# ESP32__2023-03-20.net
KiCad netlist of a schematic drawn in Altium Designer
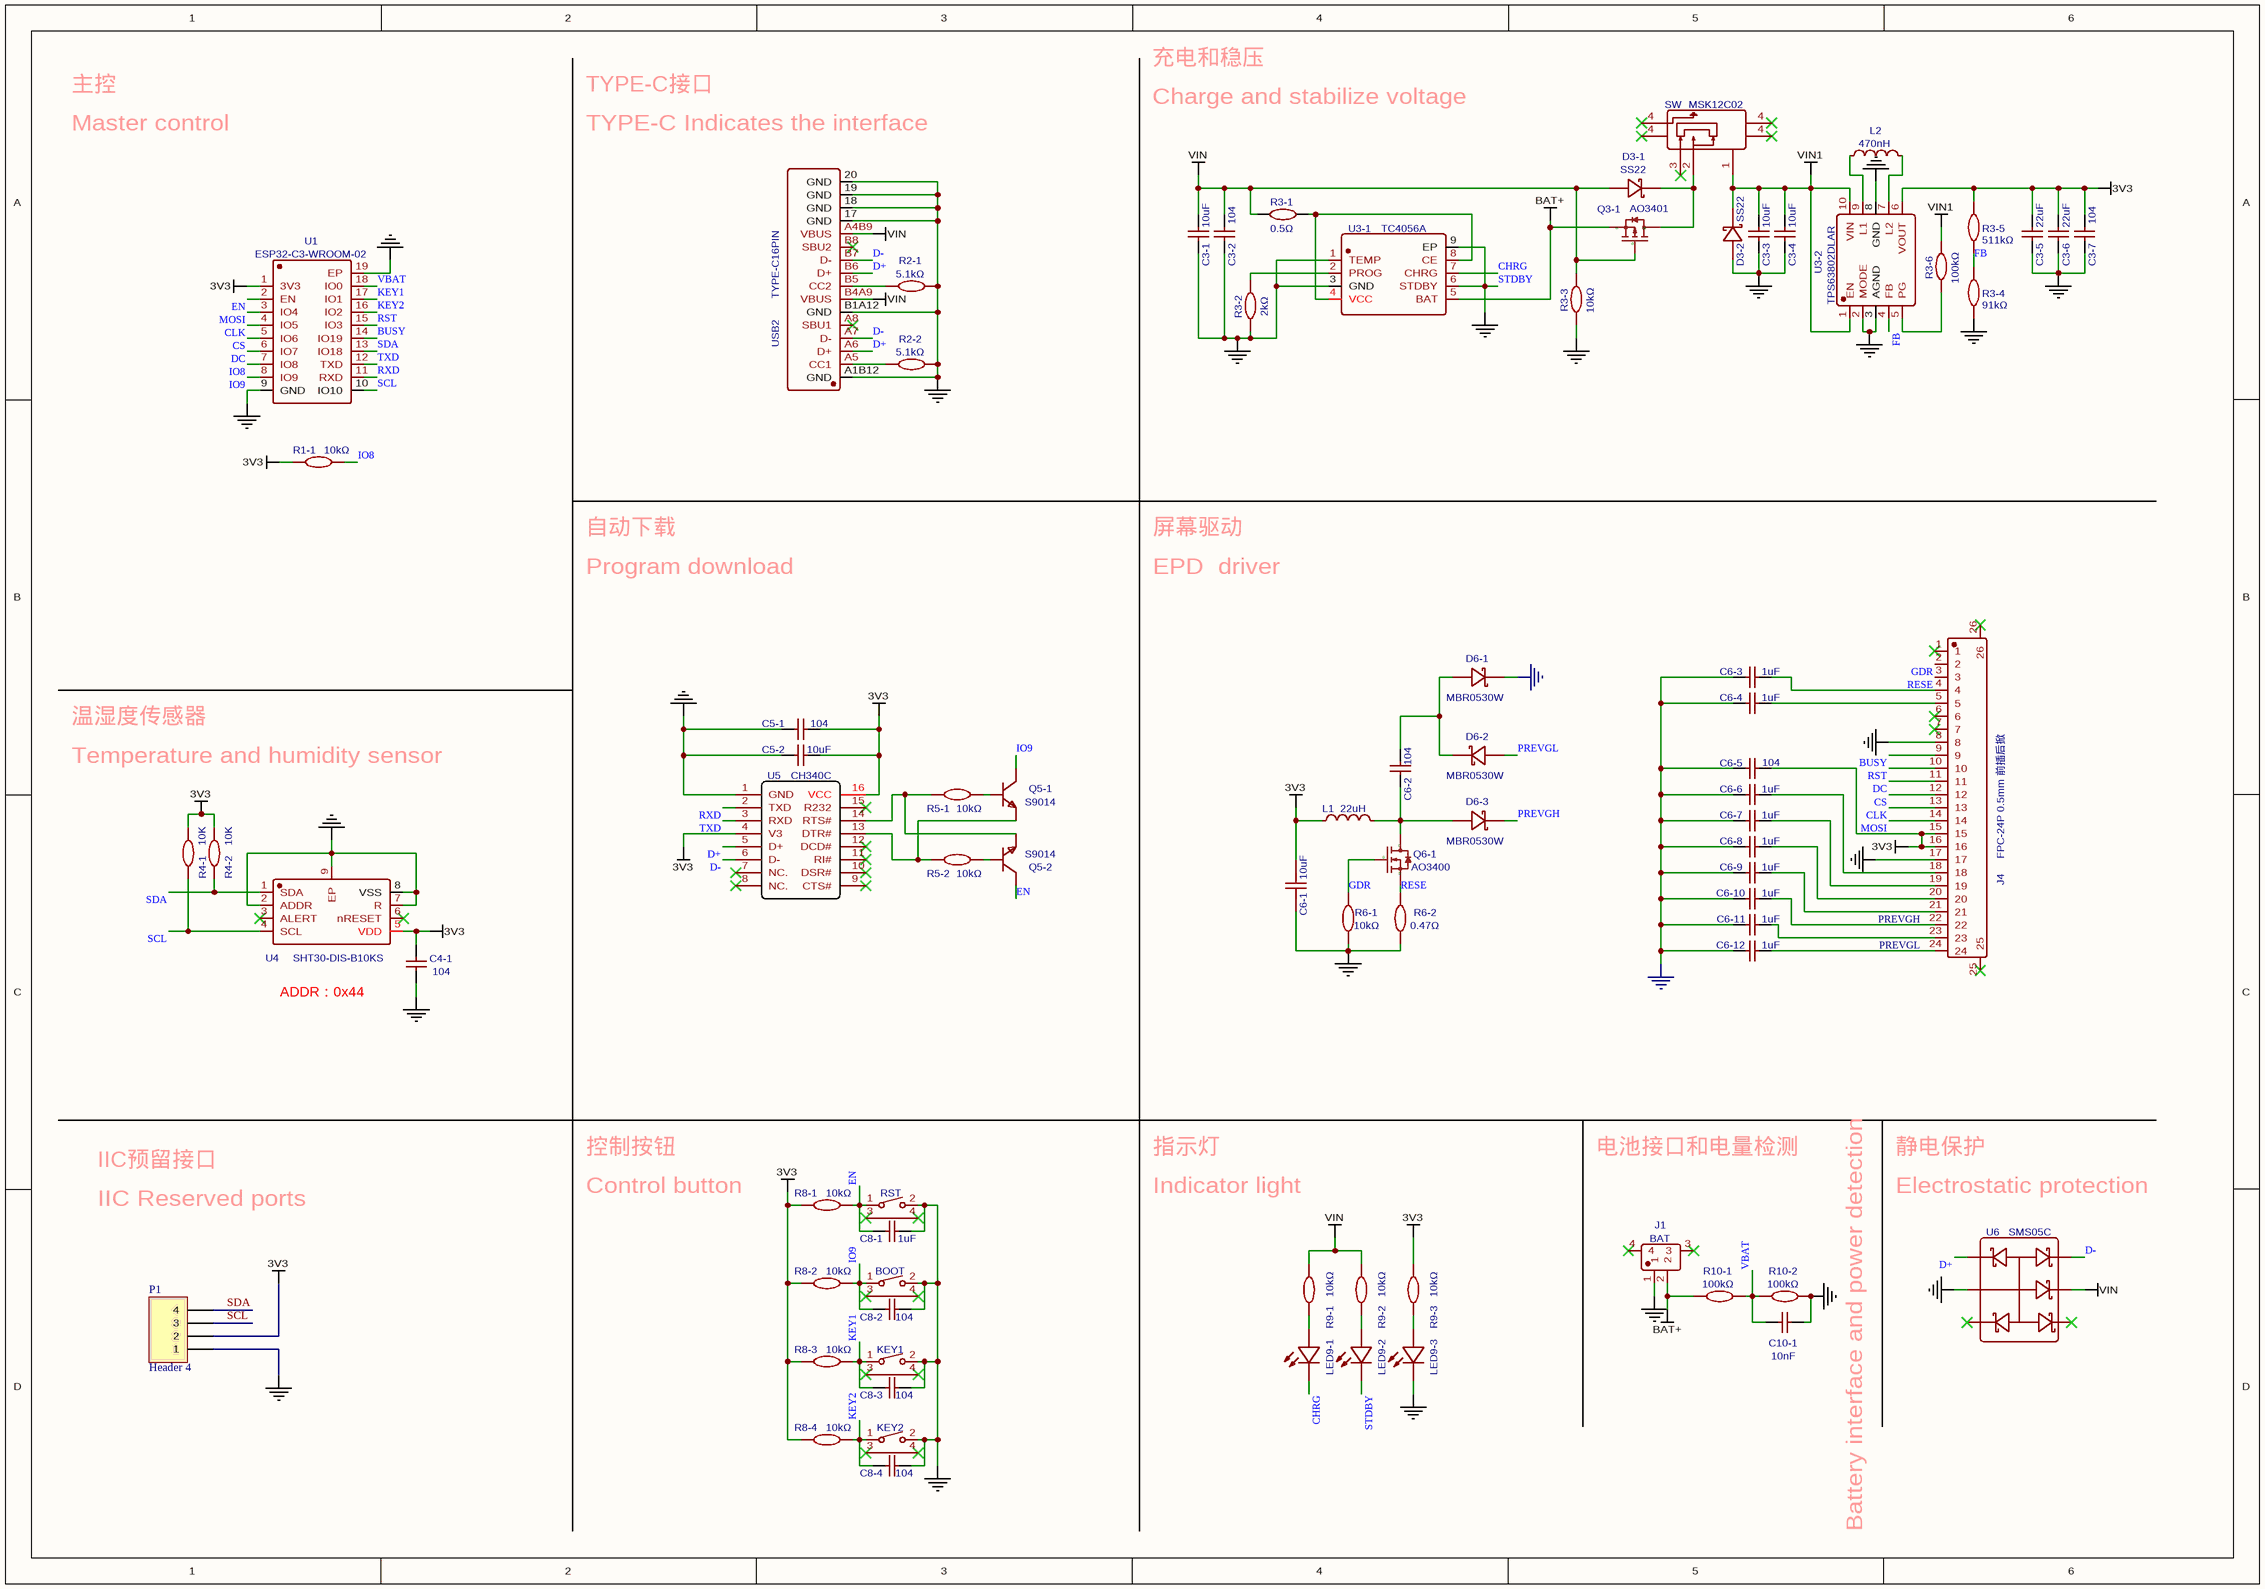
[diagram p0: ESP32墨水屏开发板_2023-03-20.schdoc]

(export (version "E")
  (design (tool "Eeschema 10.0.6"))
  (components
    (comp (ref "BOOT")
      (value "UK-B0246-SP25Y")
      (footprint "SW-SMD_UK-B0246-SP25Y")
      (fields (field (name "BOM_SUPPLIER PART") "C493279") (field (name "CONTRIBUTOR") "LCSC"))
      (libsource (lib "altium-import") (part "root_0_UK-B0246-SP25Y_"))
    )
    (comp (ref "C3-1")
      (value "10uF")
      (footprint "C0603")
      (fields
        (field (name "BOM_MANUFACTURER PART") "CC0603MRX5R5BB106")
        (field (name "BOM_SUPPLIER PART") "C109454")
      )
      (libsource (lib "altium-import") (part "root_1_10uF_"))
    )
    (comp (ref "C3-2")
      (value "104")
      (footprint "C0603")
      (fields
        (field (name "BOM_MANUFACTURER PART") "C0603C104K5RACTU")
        (field (name "BOM_SUPPLIER PART") "C127833")
        (field (name "CONTRIBUTOR") "LCSC")
      )
      (libsource (lib "altium-import") (part "root_1_104_"))
    )
    (comp (ref "C3-3")
      (value "10uF")
      (footprint "C0603")
      (fields
        (field (name "BOM_MANUFACTURER PART") "CC0603MRX5R5BB106")
        (field (name "BOM_SUPPLIER PART") "C109454")
      )
      (libsource (lib "altium-import") (part "root_1_10uF_"))
    )
    (comp (ref "C3-4")
      (value "10uF")
      (footprint "C0603")
      (fields
        (field (name "BOM_MANUFACTURER PART") "CC0603MRX5R5BB106")
        (field (name "BOM_SUPPLIER PART") "C109454")
      )
      (libsource (lib "altium-import") (part "root_1_10uF_"))
    )
    (comp (ref "C3-5")
      (value "22uF")
      (footprint "C0603")
      (fields
        (field (name "BOM_MANUFACTURER PART") "CC0603MRX5R5BB106")
        (field (name "BOM_SUPPLIER PART") "C109454")
      )
      (libsource (lib "altium-import") (part "root_1_22uF_"))
    )
    (comp (ref "C3-6")
      (value "22uF")
      (footprint "C0603")
      (fields
        (field (name "BOM_MANUFACTURER PART") "CC0603MRX5R5BB106")
        (field (name "BOM_SUPPLIER PART") "C109454")
      )
      (libsource (lib "altium-import") (part "root_1_22uF_"))
    )
    (comp (ref "C3-7")
      (value "104")
      (footprint "C0603")
      (fields
        (field (name "BOM_MANUFACTURER PART") "C0603C104K5RACTU")
        (field (name "BOM_SUPPLIER PART") "C127833")
        (field (name "CONTRIBUTOR") "LCSC")
      )
      (libsource (lib "altium-import") (part "root_1_104_"))
    )
    (comp (ref "C4-1")
      (value "104")
      (footprint "C0603")
      (fields
        (field (name "BOM_MANUFACTURER PART") "C0603C104K5RACTU")
        (field (name "BOM_SUPPLIER PART") "C127833")
        (field (name "CONTRIBUTOR") "LCSC")
      )
      (libsource (lib "altium-import") (part "root_1_104_"))
    )
    (comp (ref "C5-1")
      (value "104")
      (footprint "C0603")
      (fields
        (field (name "BOM_MANUFACTURER PART") "C0603C104K5RACTU")
        (field (name "BOM_SUPPLIER PART") "C127833")
        (field (name "CONTRIBUTOR") "LCSC")
      )
      (libsource (lib "altium-import") (part "root_2_104_"))
    )
    (comp (ref "C5-2")
      (value "10uF")
      (footprint "C0603")
      (fields
        (field (name "BOM_MANUFACTURER PART") "CC0603MRX5R5BB106")
        (field (name "BOM_SUPPLIER PART") "C109454")
      )
      (libsource (lib "altium-import") (part "root_2_10uF_"))
    )
    (comp (ref "C6-1")
      (value "10uF")
      (footprint "C0805")
      (fields
        (field (name "BOM_SUPPLIER PART") "C2844304")
        (field (name "BOM_MANUFACTURER PART") "C0805X6S106K350NT")
        (field (name "CONTRIBUTOR") "lcsc")
      )
      (libsource (lib "") (part "root_1_10uF__1"))
    )
    (comp (ref "C6-2")
      (value "104")
      (footprint "C0603")
      (fields
        (field (name "BOM_MANUFACTURER PART") "C0603C104K5RACTU")
        (field (name "BOM_SUPPLIER PART") "C127833")
        (field (name "CONTRIBUTOR") "LCSC")
      )
      (libsource (lib "altium-import") (part "root_1_104_"))
    )
    (comp (ref "C6-3")
      (value "1uF")
      (footprint "C0603")
      (fields
        (field (name "BOM_MANUFACTURER PART") "CC0603KRX5R7BB105")
        (field (name "BOM_SUPPLIER PART") "C106215")
        (field (name "CONTRIBUTOR") "LCSC")
      )
      (libsource (lib "altium-import") (part "root_0_1uF_"))
    )
    (comp (ref "C6-4")
      (value "1uF")
      (footprint "C0603")
      (fields
        (field (name "BOM_MANUFACTURER PART") "CC0603KRX5R7BB105")
        (field (name "BOM_SUPPLIER PART") "C106215")
        (field (name "CONTRIBUTOR") "LCSC")
      )
      (libsource (lib "altium-import") (part "root_0_1uF_"))
    )
    (comp (ref "C6-5")
      (value "104")
      (footprint "C0603")
      (fields
        (field (name "BOM_MANUFACTURER PART") "C0603C104K5RACTU")
        (field (name "BOM_SUPPLIER PART") "C127833")
        (field (name "CONTRIBUTOR") "LCSC")
      )
      (libsource (lib "altium-import") (part "root_2_104_"))
    )
    (comp (ref "C6-6")
      (value "1uF")
      (footprint "C0603")
      (fields
        (field (name "BOM_MANUFACTURER PART") "CC0603KRX5R7BB105")
        (field (name "BOM_SUPPLIER PART") "C106215")
        (field (name "CONTRIBUTOR") "LCSC")
      )
      (libsource (lib "altium-import") (part "root_0_1uF_"))
    )
    (comp (ref "C6-7")
      (value "1uF")
      (footprint "C0603")
      (fields
        (field (name "BOM_MANUFACTURER PART") "CC0603KRX5R7BB105")
        (field (name "BOM_SUPPLIER PART") "C106215")
        (field (name "CONTRIBUTOR") "LCSC")
      )
      (libsource (lib "altium-import") (part "root_0_1uF_"))
    )
    (comp (ref "C6-8")
      (value "1uF")
      (footprint "C0603")
      (fields
        (field (name "BOM_MANUFACTURER PART") "CC0603KRX5R7BB105")
        (field (name "BOM_SUPPLIER PART") "C106215")
        (field (name "CONTRIBUTOR") "LCSC")
      )
      (libsource (lib "altium-import") (part "root_0_1uF_"))
    )
    (comp (ref "C6-9")
      (value "1uF")
      (footprint "C0603")
      (fields
        (field (name "BOM_MANUFACTURER PART") "CC0603KRX5R7BB105")
        (field (name "BOM_SUPPLIER PART") "C106215")
        (field (name "CONTRIBUTOR") "LCSC")
      )
      (libsource (lib "altium-import") (part "root_0_1uF_"))
    )
    (comp (ref "C6-10")
      (value "1uF")
      (footprint "C0603")
      (fields
        (field (name "BOM_MANUFACTURER PART") "CC0603KRX5R7BB105")
        (field (name "BOM_SUPPLIER PART") "C106215")
        (field (name "CONTRIBUTOR") "LCSC")
      )
      (libsource (lib "altium-import") (part "root_0_1uF_"))
    )
    (comp (ref "C6-11")
      (value "1uF")
      (footprint "C0603")
      (fields
        (field (name "BOM_MANUFACTURER PART") "CC0603KRX5R7BB105")
        (field (name "BOM_SUPPLIER PART") "C106215")
        (field (name "CONTRIBUTOR") "LCSC")
      )
      (libsource (lib "altium-import") (part "root_0_1uF_"))
    )
    (comp (ref "C6-12")
      (value "1uF")
      (footprint "C0603")
      (fields
        (field (name "BOM_MANUFACTURER PART") "CC0603KRX5R7BB105")
        (field (name "BOM_SUPPLIER PART") "C106215")
        (field (name "CONTRIBUTOR") "LCSC")
      )
      (libsource (lib "altium-import") (part "root_0_1uF_"))
    )
    (comp (ref "C8-1")
      (value "1uF")
      (footprint "C0603")
      (fields
        (field (name "BOM_MANUFACTURER PART") "CC0603MRX5R5BB106")
        (field (name "BOM_SUPPLIER PART") "C109454")
      )
      (libsource (lib "altium-import") (part "root_2_1uF_"))
    )
    (comp (ref "C8-2")
      (value "104")
      (footprint "C0603")
      (fields
        (field (name "BOM_MANUFACTURER PART") "C0603C104K5RACTU")
        (field (name "BOM_SUPPLIER PART") "C127833")
        (field (name "CONTRIBUTOR") "LCSC")
      )
      (libsource (lib "altium-import") (part "root_0_104_"))
    )
    (comp (ref "C8-3")
      (value "104")
      (footprint "C0603")
      (fields
        (field (name "BOM_MANUFACTURER PART") "C0603C104K5RACTU")
        (field (name "BOM_SUPPLIER PART") "C127833")
        (field (name "CONTRIBUTOR") "LCSC")
      )
      (libsource (lib "altium-import") (part "root_0_104_"))
    )
    (comp (ref "C8-4")
      (value "104")
      (footprint "C0603")
      (fields
        (field (name "BOM_MANUFACTURER PART") "C0603C104K5RACTU")
        (field (name "BOM_SUPPLIER PART") "C127833")
        (field (name "CONTRIBUTOR") "LCSC")
      )
      (libsource (lib "altium-import") (part "root_0_104_"))
    )
    (comp (ref "C10-1")
      (value "10nF")
      (footprint "C0603")
      (fields
        (field (name "BOM_MANUFACTURER PART") "C0603C104K5RACTU")
        (field (name "BOM_SUPPLIER PART") "C127833")
        (field (name "CONTRIBUTOR") "LCSC")
      )
      (libsource (lib "altium-import") (part "root_2_10nF_"))
    )
    (comp (ref "D3-1")
      (value "SS22")
      (footprint "SMA_L4.3-W2.5-LS5.0-R-RD")
      (fields (field (name "BOM_SUPPLIER PART") "C727054") (field (name "CONTRIBUTOR") "LCSC"))
      (libsource (lib "altium-import") (part "root_2_SS22_"))
    )
    (comp (ref "D3-2")
      (value "SS22")
      (footprint "SMA_L4.3-W2.5-LS5.0-R-RD")
      (fields (field (name "BOM_SUPPLIER PART") "C727054") (field (name "CONTRIBUTOR") "LCSC"))
      (libsource (lib "altium-import") (part "root_3_SS22_"))
    )
    (comp (ref "D6-1")
      (value "MBR0530W")
      (footprint "SOD-123_L2.7-W1.7-LS3.8-RD")
      (fields
        (field (name "BOM_SUPPLIER PART") "C2965565")
        (field (name "BOM_MANUFACTURER PART") "MBR0530W B3")
        (field (name "CONTRIBUTOR") "lcsc")
      )
      (libsource (lib "altium-import") (part "root_2_MBR0530W_"))
    )
    (comp (ref "D6-2")
      (value "MBR0530W")
      (footprint "SOD-123_L2.7-W1.7-LS3.8-RD")
      (fields
        (field (name "BOM_SUPPLIER PART") "C2965565")
        (field (name "BOM_MANUFACTURER PART") "MBR0530W B3")
        (field (name "CONTRIBUTOR") "lcsc")
      )
      (libsource (lib "altium-import") (part "root_0_MBR0530W_"))
    )
    (comp (ref "D6-3")
      (value "MBR0530W")
      (footprint "SOD-123_L2.7-W1.7-LS3.8-RD")
      (fields
        (field (name "BOM_SUPPLIER PART") "C2965565")
        (field (name "BOM_MANUFACTURER PART") "MBR0530W B3")
        (field (name "CONTRIBUTOR") "lcsc")
      )
      (libsource (lib "altium-import") (part "root_2_MBR0530W_"))
    )
    (comp (ref "J1")
      (value "BAT")
      (footprint "CONN-SMD_XH2.54-2PSMD")
      (fields
        (field (name "BOM_SUPPLIER PART") "C9900001015")
        (field (name "BOM_MANUFACTURER PART") "XH2.54-2PSMD")
        (field (name "CONTRIBUTOR") "LCSC")
      )
      (libsource (lib "altium-import") (part "root_1_BAT_"))
    )
    (comp (ref "J4")
      (value "FPC-24P 0.5mm 前插后掀")
      (footprint "FPC-SMD_X05A26H24G")
      (fields
        (field (name "BOM_SUPPLIER PART") "C519265")
        (field (name "BOM_MANUFACTURER PART") "X05A26H24G")
        (field (name "CONTRIBUTOR") "LCSC")
      )
      (libsource (lib "altium-import") (part "root_0_FPC-24P 0.5mm 前插后掀_"))
    )
    (comp (ref "KEY1")
      (value "UK-B0246-SP25Y")
      (footprint "SW-SMD_UK-B0246-SP25Y")
      (fields (field (name "BOM_SUPPLIER PART") "C493279") (field (name "CONTRIBUTOR") "LCSC"))
      (libsource (lib "altium-import") (part "root_0_UK-B0246-SP25Y_"))
    )
    (comp (ref "KEY2")
      (value "UK-B0246-SP25Y")
      (footprint "SW-SMD_UK-B0246-SP25Y")
      (fields (field (name "BOM_SUPPLIER PART") "C493279") (field (name "CONTRIBUTOR") "LCSC"))
      (libsource (lib "altium-import") (part "root_0_UK-B0246-SP25Y_"))
    )
    (comp (ref "L1")
      (value "22uH")
      (footprint "IND-SMD_L2.5-W2.0_SWPA252012S")
      (fields
        (field (name "BOM_SUPPLIER PART") "C363229")
        (field (name "BOM_MANUFACTURER PART") "SMNR252012-220MT")
        (field (name "CONTRIBUTOR") "LCSC")
      )
      (libsource (lib "altium-import") (part "root_0_22uH_"))
    )
    (comp (ref "L2")
      (value "470nH")
      (footprint "L0805")
      (fields
        (field (name "BOM_MANUFACTURER PART") "SDFL2012LR47KTF")
        (field (name "BOM_SUPPLIER PART") "C48556")
      )
      (libsource (lib "altium-import") (part "root_0_470nH_"))
    )
    (comp (ref "LED9-1")
      (value "RED")
      (footprint "LED0603-RD")
      (fields
        (field (name "BOM_SUPPLIER PART") "C401120")
        (field (name "BOM_MANUFACTURER PART") "MHT192JRCT")
        (field (name "CONTRIBUTOR") "LCSC")
      )
      (libsource (lib "altium-import") (part "root_1_RED_"))
    )
    (comp (ref "LED9-2")
      (value "RED")
      (footprint "LED0603-RD")
      (fields
        (field (name "BOM_SUPPLIER PART") "C401120")
        (field (name "BOM_MANUFACTURER PART") "MHT192JRCT")
        (field (name "CONTRIBUTOR") "LCSC")
      )
      (libsource (lib "altium-import") (part "root_1_RED_"))
    )
    (comp (ref "LED9-3")
      (value "RED")
      (footprint "LED0603-RD")
      (fields
        (field (name "BOM_SUPPLIER PART") "C401120")
        (field (name "BOM_MANUFACTURER PART") "MHT192JRCT")
        (field (name "CONTRIBUTOR") "LCSC")
      )
      (libsource (lib "altium-import") (part "root_1_RED_"))
    )
    (comp (ref "P1")
      (value "Header 4")
      (footprint "HDR1X4")
      (description "Header, 4-Pin")
      (fields (field (name "PUBLISHER") "Altium Limited"))
      (libsource (lib "Miscellaneous Connectors") (part "Header 4"))
    )
    (comp (ref "Q3-1")
      (value "AO3401")
      (footprint "SOT-23-3_L2.9-W1.3-P1.90-LS2.4-BR")
      (fields (field (name "BOM_SUPPLIER PART") "C181091") (field (name "CONTRIBUTOR") "LCSC"))
      (libsource (lib "altium-import") (part "root_1_AO3401_"))
    )
    (comp (ref "Q5-1")
      (value "S9014")
      (footprint "SOT-23-3_L2.9-W1.3-P1.90-LS2.4-BR")
      (fields (field (name "BOM_SUPPLIER PART") "C2926162") (field (name "CONTRIBUTOR") "LCSC"))
      (libsource (lib "altium-import") (part "root_0_S9014_"))
    )
    (comp (ref "Q5-2")
      (value "S9014")
      (footprint "SOT-23-3_L2.9-W1.3-P1.90-LS2.4-BR")
      (fields (field (name "BOM_SUPPLIER PART") "C2926162") (field (name "CONTRIBUTOR") "LCSC"))
      (libsource (lib "") (part "root_0_S9014__1"))
    )
    (comp (ref "Q6-1")
      (value "AO3400")
      (footprint "SC-59-3_L2.9-W1.5-P0.95-LS2.5-BR")
      (fields (field (name "BOM_SUPPLIER PART") "C122850") (field (name "CONTRIBUTOR") "立创EDA官方封装库"))
      (libsource (lib "altium-import") (part "root_0_AO3400_"))
    )
    (comp (ref "R1-1")
      (value "10kΩ")
      (footprint "R0603")
      (fields
        (field (name "BOM_SUPPLIER PART") "C380762")
        (field (name "BOM_MANUFACTURER PART") "SY0603JN10KP")
        (field (name "CONTRIBUTOR") "LCSC")
      )
      (libsource (lib "altium-import") (part "root_2_10kΩ_"))
    )
    (comp (ref "R2-1")
      (value "5.1kΩ")
      (footprint "R0603")
      (fields
        (field (name "BOM_SUPPLIER PART") "C369945")
        (field (name "BOM_MANUFACTURER PART") "PTFR0603D5K10P9")
        (field (name "CONTRIBUTOR") "LCSC")
      )
      (libsource (lib "altium-import") (part "root_0_5.1kΩ_"))
    )
    (comp (ref "R2-2")
      (value "5.1kΩ")
      (footprint "R0603")
      (fields
        (field (name "BOM_SUPPLIER PART") "C369945")
        (field (name "BOM_MANUFACTURER PART") "PTFR0603D5K10P9")
        (field (name "CONTRIBUTOR") "LCSC")
      )
      (libsource (lib "altium-import") (part "root_0_5.1kΩ_"))
    )
    (comp (ref "R3-1")
      (value "0.5Ω")
      (footprint "R1206")
      (fields
        (field (name "BOM_MANUFACTURER PART") "RTT06R500FTP")
        (field (name "BOM_SUPPLIER PART") "C104947")
      )
      (libsource (lib "altium-import") (part "root_2_0.5Ω_"))
    )
    (comp (ref "R3-2")
      (value "2kΩ")
      (footprint "R0603")
      (fields
        (field (name "BOM_SUPPLIER PART") "C380762")
        (field (name "BOM_MANUFACTURER PART") "SY0603JN10KP")
        (field (name "CONTRIBUTOR") "LCSC")
      )
      (libsource (lib "altium-import") (part "root_1_2kΩ_"))
    )
    (comp (ref "R3-3")
      (value "10kΩ")
      (footprint "R0603")
      (fields
        (field (name "BOM_SUPPLIER PART") "C380762")
        (field (name "BOM_MANUFACTURER PART") "SY0603JN10KP")
        (field (name "CONTRIBUTOR") "LCSC")
      )
      (libsource (lib "altium-import") (part "root_1_10kΩ_"))
    )
    (comp (ref "R3-4")
      (value "91kΩ")
      (footprint "R0603")
      (fields
        (field (name "BOM_SUPPLIER PART") "C369945")
        (field (name "BOM_MANUFACTURER PART") "PTFR0603D5K10P9")
        (field (name "CONTRIBUTOR") "LCSC")
      )
      (libsource (lib "altium-import") (part "root_3_91kΩ_"))
    )
    (comp (ref "R3-5")
      (value "511kΩ")
      (footprint "R0603")
      (fields
        (field (name "BOM_SUPPLIER PART") "C369945")
        (field (name "BOM_MANUFACTURER PART") "PTFR0603D5K10P9")
        (field (name "CONTRIBUTOR") "LCSC")
      )
      (libsource (lib "altium-import") (part "root_3_511kΩ_"))
    )
    (comp (ref "R3-6")
      (value "100kΩ")
      (footprint "R0603")
      (fields
        (field (name "BOM_SUPPLIER PART") "C380762")
        (field (name "BOM_MANUFACTURER PART") "SY0603JN10KP")
        (field (name "CONTRIBUTOR") "LCSC")
      )
      (libsource (lib "altium-import") (part "root_1_100kΩ_"))
    )
    (comp (ref "R4-1")
      (value "10K")
      (footprint "R0603")
      (fields
        (field (name "BOM_SUPPLIER PART") "C380762")
        (field (name "BOM_MANUFACTURER PART") "SY0603JN10KP")
        (field (name "CONTRIBUTOR") "LCSC")
      )
      (libsource (lib "altium-import") (part "root_1_10K_"))
    )
    (comp (ref "R4-2")
      (value "10K")
      (footprint "R0603")
      (fields
        (field (name "BOM_SUPPLIER PART") "C380762")
        (field (name "BOM_MANUFACTURER PART") "SY0603JN10KP")
        (field (name "CONTRIBUTOR") "LCSC")
      )
      (libsource (lib "altium-import") (part "root_1_10K_"))
    )
    (comp (ref "R5-1")
      (value "10kΩ")
      (footprint "R0603")
      (fields
        (field (name "BOM_SUPPLIER PART") "C380762")
        (field (name "BOM_MANUFACTURER PART") "SY0603JN10KP")
        (field (name "CONTRIBUTOR") "LCSC")
      )
      (libsource (lib "altium-import") (part "root_0_10kΩ_"))
    )
    (comp (ref "R5-2")
      (value "10kΩ")
      (footprint "R0603")
      (fields
        (field (name "BOM_SUPPLIER PART") "C380762")
        (field (name "BOM_MANUFACTURER PART") "SY0603JN10KP")
        (field (name "CONTRIBUTOR") "LCSC")
      )
      (libsource (lib "altium-import") (part "root_0_10kΩ_"))
    )
    (comp (ref "R6-1")
      (value "10kΩ")
      (footprint "R0603")
      (fields
        (field (name "BOM_SUPPLIER PART") "C380762")
        (field (name "BOM_MANUFACTURER PART") "SY0603JN10KP")
        (field (name "CONTRIBUTOR") "LCSC")
      )
      (libsource (lib "altium-import") (part "root_1_10kΩ_"))
    )
    (comp (ref "R6-2")
      (value "0.47Ω")
      (footprint "R0603")
      (fields
        (field (name "BOM_SUPPLIER PART") "C175657")
        (field (name "BOM_MANUFACTURER PART") "CR0603F0R47P05")
        (field (name "CONTRIBUTOR") "LCSC")
      )
      (libsource (lib "altium-import") (part "root_1_0.47Ω_"))
    )
    (comp (ref "R8-1")
      (value "10kΩ")
      (footprint "R0603")
      (fields
        (field (name "BOM_SUPPLIER PART") "C380762")
        (field (name "BOM_MANUFACTURER PART") "SY0603JN10KP")
        (field (name "CONTRIBUTOR") "LCSC")
      )
      (libsource (lib "altium-import") (part "root_0_10kΩ_"))
    )
    (comp (ref "R8-2")
      (value "10kΩ")
      (footprint "R0603")
      (fields
        (field (name "BOM_SUPPLIER PART") "C380762")
        (field (name "BOM_MANUFACTURER PART") "SY0603JN10KP")
        (field (name "CONTRIBUTOR") "LCSC")
      )
      (libsource (lib "altium-import") (part "root_0_10kΩ_"))
    )
    (comp (ref "R8-3")
      (value "10kΩ")
      (footprint "R0603")
      (fields
        (field (name "BOM_SUPPLIER PART") "C380762")
        (field (name "BOM_MANUFACTURER PART") "SY0603JN10KP")
        (field (name "CONTRIBUTOR") "LCSC")
      )
      (libsource (lib "altium-import") (part "root_0_10kΩ_"))
    )
    (comp (ref "R8-4")
      (value "10kΩ")
      (footprint "R0603")
      (fields
        (field (name "BOM_SUPPLIER PART") "C380762")
        (field (name "BOM_MANUFACTURER PART") "SY0603JN10KP")
        (field (name "CONTRIBUTOR") "LCSC")
      )
      (libsource (lib "altium-import") (part "root_0_10kΩ_"))
    )
    (comp (ref "R9-1")
      (value "10kΩ")
      (footprint "R0603")
      (fields
        (field (name "BOM_SUPPLIER PART") "C380762")
        (field (name "BOM_MANUFACTURER PART") "SY0603JN10KP")
        (field (name "CONTRIBUTOR") "LCSC")
      )
      (libsource (lib "altium-import") (part "root_1_10kΩ_"))
    )
    (comp (ref "R9-2")
      (value "10kΩ")
      (footprint "R0603")
      (fields
        (field (name "BOM_SUPPLIER PART") "C380762")
        (field (name "BOM_MANUFACTURER PART") "SY0603JN10KP")
        (field (name "CONTRIBUTOR") "LCSC")
      )
      (libsource (lib "altium-import") (part "root_1_10kΩ_"))
    )
    (comp (ref "R9-3")
      (value "10kΩ")
      (footprint "R0603")
      (fields
        (field (name "BOM_SUPPLIER PART") "C380762")
        (field (name "BOM_MANUFACTURER PART") "SY0603JN10KP")
        (field (name "CONTRIBUTOR") "LCSC")
      )
      (libsource (lib "altium-import") (part "root_1_10kΩ_"))
    )
    (comp (ref "R10-1")
      (value "100kΩ")
      (footprint "R0603")
      (fields
        (field (name "BOM_SUPPLIER PART") "C269694")
        (field (name "BOM_MANUFACTURER PART") "RMC06034.7k5%N")
        (field (name "CONTRIBUTOR") "LCSC")
      )
      (libsource (lib "altium-import") (part "root_2_100kΩ_"))
    )
    (comp (ref "R10-2")
      (value "100kΩ")
      (footprint "R0603")
      (fields
        (field (name "BOM_SUPPLIER PART") "C328340")
        (field (name "BOM_MANUFACTURER PART") "AECR0603F1K00K9")
        (field (name "CONTRIBUTOR") "LCSC")
      )
      (libsource (lib "altium-import") (part "root_2_100kΩ_"))
    )
    (comp (ref "RST")
      (value "UK-B0246-SP25Y")
      (footprint "SW-SMD_UK-B0246-SP25Y")
      (fields (field (name "BOM_SUPPLIER PART") "C493279") (field (name "CONTRIBUTOR") "LCSC"))
      (libsource (lib "altium-import") (part "root_0_UK-B0246-SP25Y_"))
    )
    (comp (ref "SW")
      (value "MSK12C02")
      (footprint "SW-TH_MSK12C02")
      (fields (field (name "BOM_SUPPLIER PART") "C431540") (field (name "CONTRIBUTOR") "LCSC"))
      (libsource (lib "altium-import") (part "root_2_MSK12C02_"))
    )
    (comp (ref "U1")
      (value "ESP32-C3-WROOM-02")
      (footprint "BULETM-SMD_ESPRESSIF_ESP32-C3-WROOM-02-N4-4MB")
      (fields
        (field (name "BOM_SUPPLIER PART") "C2934560")
        (field (name "BOM_MANUFACTURER PART") "ESP32-C3-WROOM-02-N4")
        (field (name "CONTRIBUTOR") "LCSC")
      )
      (libsource (lib "altium-import") (part "root_0_ESP32-C3-WROOM-02_"))
    )
    (comp (ref "U3-1")
      (value "TC4056A")
      (footprint "SOP-8_L4.9-W3.9-P1.27-LS6.0-BL-EP")
      (fields (field (name "BOM_SUPPLIER PART") "C84051"))
      (libsource (lib "altium-import") (part "root_0_TC4056A_"))
    )
    (comp (ref "U3-2")
      (value "TPS63802DLAR")
      (footprint "VSON-10_L3.0-W2.0-P0.50-BL_TI_DLA0010A")
      (fields (field (name "BOM_SUPPLIER PART") "C2845237") (field (name "CONTRIBUTOR") "LCSC"))
      (libsource (lib "altium-import") (part "root_1_TPS63802DLAR_"))
    )
    (comp (ref "U4")
      (value "SHT30-DIS-B10KS")
      (footprint "DFN-8_L2.5-W2.5-P0.50-BL-EP")
      (fields (field (name "BOM_SUPPLIER PART") "C2687423") (field (name "CONTRIBUTOR") "LCSC"))
      (libsource (lib "altium-import") (part "root_0_SHT30-DIS-B10KS_"))
    )
    (comp (ref "U5")
      (value "CH340C")
      (footprint "SOP-16_L10.0-W3.9-P1.27-LS6.0-BL")
      (fields (field (name "BOM_SUPPLIER PART") "C84681"))
      (libsource (lib "altium-import") (part "root_0_CH340C_"))
    )
    (comp (ref "U6")
      (value "SMS05C")
      (footprint "SOT-23-6_L2.9-W1.6-P0.95-LS2.8-BL")
      (fields (field (name "BOM_SUPPLIER PART") "C2827671") (field (name "CONTRIBUTOR") "lcsc"))
      (libsource (lib "altium-import") (part "root_0_SMS05C_"))
    )
    (comp (ref "USB2")
      (value "TYPE-C16PIN")
      (footprint "USB-SMD_TYPE-C16PIN-1")
      (fields
        (field (name "BOM_SUPPLIER PART") "C2894751")
        (field (name "BOM_MANUFACTURER PART") "TYPE-C16PIN四脚插板母座5A大电流")
        (field (name "CONTRIBUTOR") "LCSC")
      )
      (libsource (lib "altium-import") (part "root_2_TYPE-C16PIN_"))
    )
  )
  (nets
    (net (code "1") (name "/BUSY") (class "Default")
      (node (ref "J4") (pin "9") (pinfunction "9_9") (pintype "passive"))
      (node (ref "U1") (pin "14") (pinfunction "IO19_14") (pintype "passive"))
    )
    (net (code "2") (name "/CHRG") (class "Default")
      (node (ref "LED9-1") (pin "1") (pinfunction "K_1") (pintype "passive"))
      (node (ref "U3-1") (pin "7") (pinfunction "CHRG_7") (pintype "passive"))
    )
    (net (code "3") (name "/CLK") (class "Default")
      (node (ref "J4") (pin "13") (pinfunction "13_13") (pintype "passive"))
      (node (ref "U1") (pin "4") (pinfunction "IO5_4") (pintype "passive"))
    )
    (net (code "4") (name "/CS") (class "Default")
      (node (ref "J4") (pin "12") (pinfunction "12_12") (pintype "passive"))
      (node (ref "U1") (pin "5") (pinfunction "IO6_5") (pintype "passive"))
    )
    (net (code "5") (name "/D+") (class "Default")
      (node (ref "U5") (pin "5") (pinfunction "D+_5") (pintype "passive"))
      (node (ref "U6") (pin "1") (pinfunction "1_1") (pintype "passive"))
      (node (ref "USB2") (pin "A6") (pinfunction "D+_A6") (pintype "passive"))
      (node (ref "USB2") (pin "B6") (pinfunction "D+_B6") (pintype "passive"))
    )
    (net (code "6") (name "/D-") (class "Default")
      (node (ref "U5") (pin "6") (pinfunction "D-_6") (pintype "passive"))
      (node (ref "U6") (pin "6") (pinfunction "6_6") (pintype "passive"))
      (node (ref "USB2") (pin "A7") (pinfunction "D-_A7") (pintype "passive"))
      (node (ref "USB2") (pin "B7") (pinfunction "D-_B7") (pintype "passive"))
    )
    (net (code "7") (name "/DC") (class "Default")
      (node (ref "J4") (pin "11") (pinfunction "11_11") (pintype "passive"))
      (node (ref "U1") (pin "6") (pinfunction "IO7_6") (pintype "passive"))
    )
    (net (code "8") (name "/EN") (class "Default")
      (node (ref "C8-1") (pin "2") (pinfunction "2_2") (pintype "passive"))
      (node (ref "Q5-2") (pin "3") (pinfunction "C_3") (pintype "passive"))
      (node (ref "R8-1") (pin "2") (pinfunction "2_2") (pintype "passive"))
      (node (ref "RST") (pin "1") (pinfunction "1_1") (pintype "passive"))
      (node (ref "U1") (pin "2") (pinfunction "EN_2") (pintype "passive"))
    )
    (net (code "9") (name "/FB") (class "Default")
      (node (ref "R3-4") (pin "1") (pinfunction "1_1") (pintype "passive"))
      (node (ref "R3-5") (pin "2") (pinfunction "2_2") (pintype "passive"))
      (node (ref "U3-2") (pin "4") (pinfunction "FB_4") (pintype "passive"))
    )
    (net (code "10") (name "/GDR") (class "Default")
      (node (ref "J4") (pin "2") (pinfunction "2_2") (pintype "passive"))
      (node (ref "Q6-1") (pin "1") (pinfunction "G_1") (pintype "passive"))
      (node (ref "R6-1") (pin "2") (pinfunction "2_2") (pintype "passive"))
    )
    (net (code "11") (name "/IO8") (class "Default")
      (node (ref "R1-1") (pin "1") (pinfunction "1_1") (pintype "passive"))
      (node (ref "U1") (pin "7") (pinfunction "IO8_7") (pintype "passive"))
    )
    (net (code "12") (name "/IO9") (class "Default")
      (node (ref "BOOT") (pin "1") (pinfunction "1_1") (pintype "passive"))
      (node (ref "C8-2") (pin "1") (pinfunction "1_1") (pintype "passive"))
      (node (ref "Q5-1") (pin "3") (pinfunction "C_3") (pintype "passive"))
      (node (ref "R8-2") (pin "2") (pinfunction "2_2") (pintype "passive"))
      (node (ref "U1") (pin "8") (pinfunction "IO9_8") (pintype "passive"))
    )
    (net (code "13") (name "/KEY1") (class "Default")
      (node (ref "C8-3") (pin "1") (pinfunction "1_1") (pintype "passive"))
      (node (ref "KEY1") (pin "1") (pinfunction "1_1") (pintype "passive"))
      (node (ref "R8-3") (pin "2") (pinfunction "2_2") (pintype "passive"))
      (node (ref "U1") (pin "17") (pinfunction "IO1_17") (pintype "passive"))
    )
    (net (code "14") (name "/KEY2") (class "Default")
      (node (ref "C8-4") (pin "1") (pinfunction "1_1") (pintype "passive"))
      (node (ref "KEY2") (pin "1") (pinfunction "1_1") (pintype "passive"))
      (node (ref "R8-4") (pin "2") (pinfunction "2_2") (pintype "passive"))
      (node (ref "U1") (pin "16") (pinfunction "IO2_16") (pintype "passive"))
    )
    (net (code "15") (name "/MOSI") (class "Default")
      (node (ref "J4") (pin "14") (pinfunction "14_14") (pintype "passive"))
      (node (ref "U1") (pin "3") (pinfunction "IO4_3") (pintype "passive"))
    )
    (net (code "16") (name "/PREVGH") (class "Default")
      (node (ref "C6-9") (pin "2") (pinfunction "2_2") (pintype "passive"))
      (node (ref "D6-3") (pin "1") (pinfunction "1_1") (pintype "passive"))
      (node (ref "J4") (pin "21") (pinfunction "21_21") (pintype "passive"))
    )
    (net (code "17") (name "/PREVGL") (class "Default")
      (node (ref "C6-11") (pin "2") (pinfunction "2_2") (pintype "passive"))
      (node (ref "D6-2") (pin "2") (pinfunction "2_2") (pintype "passive"))
      (node (ref "J4") (pin "23") (pinfunction "23_23") (pintype "passive"))
    )
    (net (code "18") (name "/RESE") (class "Default")
      (node (ref "J4") (pin "3") (pinfunction "3_3") (pintype "passive"))
      (node (ref "Q6-1") (pin "2") (pinfunction "S_2") (pintype "passive"))
      (node (ref "R6-2") (pin "2") (pinfunction "2_2") (pintype "passive"))
    )
    (net (code "19") (name "/RST") (class "Default")
      (node (ref "J4") (pin "10") (pinfunction "10_10") (pintype "passive"))
      (node (ref "U1") (pin "15") (pinfunction "IO3_15") (pintype "passive"))
    )
    (net (code "20") (name "/RXD") (class "Default")
      (node (ref "U1") (pin "11") (pinfunction "RXD_11") (pintype "passive"))
      (node (ref "U5") (pin "2") (pinfunction "TXD_2") (pintype "passive"))
    )
    (net (code "21") (name "/SCL") (class "Default")
      (node (ref "P1") (pin "3") (pinfunction "3_3") (pintype "passive"))
      (node (ref "R4-1") (pin "1") (pinfunction "1_1") (pintype "passive"))
      (node (ref "U1") (pin "10") (pinfunction "IO10_10") (pintype "passive"))
      (node (ref "U4") (pin "4") (pinfunction "SCL_4") (pintype "passive"))
    )
    (net (code "22") (name "/SDA") (class "Default")
      (node (ref "P1") (pin "4") (pinfunction "4_4") (pintype "passive"))
      (node (ref "R4-2") (pin "1") (pinfunction "1_1") (pintype "passive"))
      (node (ref "U1") (pin "13") (pinfunction "IO18_13") (pintype "passive"))
      (node (ref "U4") (pin "1") (pinfunction "SDA_1") (pintype "passive"))
    )
    (net (code "23") (name "/TXD") (class "Default")
      (node (ref "U1") (pin "12") (pinfunction "TXD_12") (pintype "passive"))
      (node (ref "U5") (pin "3") (pinfunction "RXD_3") (pintype "passive"))
    )
    (net (code "24") (name "/VBAT") (class "Default")
      (node (ref "C10-1") (pin "2") (pinfunction "2_2") (pintype "passive"))
      (node (ref "R10-1") (pin "1") (pinfunction "1_1") (pintype "passive"))
      (node (ref "R10-2") (pin "2") (pinfunction "2_2") (pintype "passive"))
      (node (ref "U1") (pin "18") (pinfunction "IO0_18") (pintype "passive"))
    )
    (net (code "25") (name "3V3") (class "Default")
      (node (ref "C3-5") (pin "2") (pinfunction "2_2") (pintype "passive"))
      (node (ref "C3-6") (pin "2") (pinfunction "2_2") (pintype "passive"))
      (node (ref "C3-7") (pin "2") (pinfunction "2_2") (pintype "passive"))
      (node (ref "C4-1") (pin "2") (pinfunction "2_2") (pintype "passive"))
      (node (ref "C5-1") (pin "1") (pinfunction "1_1") (pintype "passive"))
      (node (ref "C5-2") (pin "1") (pinfunction "1_1") (pintype "passive"))
      (node (ref "C6-1") (pin "2") (pinfunction "2_2") (pintype "passive"))
      (node (ref "C6-5") (pin "1") (pinfunction "1_1") (pintype "passive"))
      (node (ref "J4") (pin "15") (pinfunction "15_15") (pintype "passive"))
      (node (ref "J4") (pin "16") (pinfunction "16_16") (pintype "passive"))
      (node (ref "L1") (pin "1") (pinfunction "1_1") (pintype "passive"))
      (node (ref "P1") (pin "2") (pinfunction "2_2") (pintype "passive"))
      (node (ref "R1-1") (pin "2") (pinfunction "2_2") (pintype "passive"))
      (node (ref "R3-5") (pin "1") (pinfunction "1_1") (pintype "passive"))
      (node (ref "R4-1") (pin "2") (pinfunction "2_2") (pintype "passive"))
      (node (ref "R4-2") (pin "2") (pinfunction "2_2") (pintype "passive"))
      (node (ref "R8-1") (pin "1") (pinfunction "1_1") (pintype "passive"))
      (node (ref "R8-2") (pin "1") (pinfunction "1_1") (pintype "passive"))
      (node (ref "R8-3") (pin "1") (pinfunction "1_1") (pintype "passive"))
      (node (ref "R8-4") (pin "1") (pinfunction "1_1") (pintype "passive"))
      (node (ref "R9-3") (pin "2") (pinfunction "2_2") (pintype "passive"))
      (node (ref "U1") (pin "1") (pinfunction "3V3_1") (pintype "passive"))
      (node (ref "U3-2") (pin "6") (pinfunction "VOUT_6") (pintype "passive"))
      (node (ref "U4") (pin "5") (pinfunction "VDD_5") (pintype "passive"))
      (node (ref "U5") (pin "16") (pinfunction "VCC_16") (pintype "passive"))
      (node (ref "U5") (pin "4") (pinfunction "V3_4") (pintype "passive"))
    )
    (net (code "26") (name "BAT+") (class "Default")
      (node (ref "J1") (pin "2") (pinfunction "2_2") (pintype "passive"))
      (node (ref "Q3-1") (pin "2") (pinfunction "S_2") (pintype "passive"))
      (node (ref "R10-1") (pin "2") (pinfunction "2_2") (pintype "passive"))
      (node (ref "U3-1") (pin "5") (pinfunction "BAT_5") (pintype "passive"))
    )
    (net (code "27") (name "GND") (class "Default")
      (node (ref "BOOT") (pin "2") (pinfunction "2_2") (pintype "passive"))
      (node (ref "C10-1") (pin "1") (pinfunction "1_1") (pintype "passive"))
      (node (ref "C3-1") (pin "1") (pinfunction "1_1") (pintype "passive"))
      (node (ref "C3-2") (pin "1") (pinfunction "1_1") (pintype "passive"))
      (node (ref "C3-3") (pin "1") (pinfunction "1_1") (pintype "passive"))
      (node (ref "C3-4") (pin "1") (pinfunction "1_1") (pintype "passive"))
      (node (ref "C3-5") (pin "1") (pinfunction "1_1") (pintype "passive"))
      (node (ref "C3-6") (pin "1") (pinfunction "1_1") (pintype "passive"))
      (node (ref "C3-7") (pin "1") (pinfunction "1_1") (pintype "passive"))
      (node (ref "C4-1") (pin "1") (pinfunction "1_1") (pintype "passive"))
      (node (ref "C5-1") (pin "2") (pinfunction "2_2") (pintype "passive"))
      (node (ref "C5-2") (pin "2") (pinfunction "2_2") (pintype "passive"))
      (node (ref "C6-1") (pin "1") (pinfunction "1_1") (pintype "passive"))
      (node (ref "C6-10") (pin "1") (pinfunction "1_1") (pintype "passive"))
      (node (ref "C6-11") (pin "1") (pinfunction "1_1") (pintype "passive"))
      (node (ref "C6-12") (pin "1") (pinfunction "1_1") (pintype "passive"))
      (node (ref "C6-3") (pin "1") (pinfunction "1_1") (pintype "passive"))
      (node (ref "C6-4") (pin "1") (pinfunction "1_1") (pintype "passive"))
      (node (ref "C6-5") (pin "2") (pinfunction "2_2") (pintype "passive"))
      (node (ref "C6-6") (pin "1") (pinfunction "1_1") (pintype "passive"))
      (node (ref "C6-7") (pin "1") (pinfunction "1_1") (pintype "passive"))
      (node (ref "C6-8") (pin "1") (pinfunction "1_1") (pintype "passive"))
      (node (ref "C6-9") (pin "1") (pinfunction "1_1") (pintype "passive"))
      (node (ref "C8-1") (pin "1") (pinfunction "1_1") (pintype "passive"))
      (node (ref "C8-2") (pin "2") (pinfunction "2_2") (pintype "passive"))
      (node (ref "C8-3") (pin "2") (pinfunction "2_2") (pintype "passive"))
      (node (ref "C8-4") (pin "2") (pinfunction "2_2") (pintype "passive"))
      (node (ref "D3-2") (pin "1") (pinfunction "A_1") (pintype "passive"))
      (node (ref "D6-1") (pin "1") (pinfunction "1_1") (pintype "passive"))
      (node (ref "J1") (pin "1") (pinfunction "1_1") (pintype "passive"))
      (node (ref "J4") (pin "17") (pinfunction "17_17") (pintype "passive"))
      (node (ref "J4") (pin "8") (pinfunction "8_8") (pintype "passive"))
      (node (ref "KEY1") (pin "2") (pinfunction "2_2") (pintype "passive"))
      (node (ref "KEY2") (pin "2") (pinfunction "2_2") (pintype "passive"))
      (node (ref "LED9-2") (pin "1") (pinfunction "K_1") (pintype "passive"))
      (node (ref "LED9-3") (pin "1") (pinfunction "K_1") (pintype "passive"))
      (node (ref "P1") (pin "1") (pinfunction "1_1") (pintype "passive"))
      (node (ref "R10-2") (pin "1") (pinfunction "1_1") (pintype "passive"))
      (node (ref "R2-1") (pin "2") (pinfunction "2_2") (pintype "passive"))
      (node (ref "R2-2") (pin "2") (pinfunction "2_2") (pintype "passive"))
      (node (ref "R3-2") (pin "1") (pinfunction "1_1") (pintype "passive"))
      (node (ref "R3-3") (pin "1") (pinfunction "1_1") (pintype "passive"))
      (node (ref "R3-4") (pin "2") (pinfunction "2_2") (pintype "passive"))
      (node (ref "R6-1") (pin "1") (pinfunction "1_1") (pintype "passive"))
      (node (ref "R6-2") (pin "1") (pinfunction "1_1") (pintype "passive"))
      (node (ref "RST") (pin "2") (pinfunction "2_2") (pintype "passive"))
      (node (ref "U1") (pin "19") (pinfunction "EP_19") (pintype "passive"))
      (node (ref "U1") (pin "9") (pinfunction "GND_9") (pintype "passive"))
      (node (ref "U3-1") (pin "1") (pinfunction "TEMP_1") (pintype "passive"))
      (node (ref "U3-1") (pin "3") (pinfunction "GND_3") (pintype "passive"))
      (node (ref "U3-1") (pin "6") (pinfunction "STDBY_6") (pintype "passive"))
      (node (ref "U3-1") (pin "9") (pinfunction "EP_9") (pintype "passive"))
      (node (ref "U3-2") (pin "2") (pinfunction "MODE_2") (pintype "passive"))
      (node (ref "U3-2") (pin "3") (pinfunction "AGND_3") (pintype "passive"))
      (node (ref "U3-2") (pin "8") (pinfunction "GND_8") (pintype "passive"))
      (node (ref "U4") (pin "2") (pinfunction "ADDR_2") (pintype "passive"))
      (node (ref "U4") (pin "7") (pinfunction "R_7") (pintype "passive"))
      (node (ref "U4") (pin "8") (pinfunction "VSS_8") (pintype "passive"))
      (node (ref "U4") (pin "9") (pinfunction "EP_9") (pintype "passive"))
      (node (ref "U5") (pin "1") (pinfunction "GND_1") (pintype "passive"))
      (node (ref "U6") (pin "2") (pinfunction "2_2") (pintype "passive"))
      (node (ref "USB2") (pin "17") (pinfunction "GND_17") (pintype "passive"))
      (node (ref "USB2") (pin "18") (pinfunction "GND_18") (pintype "passive"))
      (node (ref "USB2") (pin "19") (pinfunction "GND_19") (pintype "passive"))
      (node (ref "USB2") (pin "20") (pinfunction "GND_20") (pintype "passive"))
      (node (ref "USB2") (pin "A1B12") (pinfunction "GND_A1B12") (pintype "passive"))
      (node (ref "USB2") (pin "B1A12") (pinfunction "GND_B1A12") (pintype "passive"))
    )
    (net (code "28") (name "Net-(C6-2-Pad2)") (class "Default")
      (node (ref "C6-2") (pin "2") (pinfunction "2_2") (pintype "passive"))
      (node (ref "D6-1") (pin "2") (pinfunction "2_2") (pintype "passive"))
      (node (ref "D6-2") (pin "1") (pinfunction "1_1") (pintype "passive"))
    )
    (net (code "29") (name "Net-(C6-3-Pad2)") (class "Default")
      (node (ref "C6-3") (pin "2") (pinfunction "2_2") (pintype "passive"))
      (node (ref "J4") (pin "4") (pinfunction "4_4") (pintype "passive"))
    )
    (net (code "30") (name "Net-(C6-4-Pad2)") (class "Default")
      (node (ref "C6-4") (pin "2") (pinfunction "2_2") (pintype "passive"))
      (node (ref "J4") (pin "5") (pinfunction "5_5") (pintype "passive"))
    )
    (net (code "31") (name "Net-(C6-6-Pad2)") (class "Default")
      (node (ref "C6-6") (pin "2") (pinfunction "2_2") (pintype "passive"))
      (node (ref "J4") (pin "18") (pinfunction "18_18") (pintype "passive"))
    )
    (net (code "32") (name "Net-(C6-7-Pad2)") (class "Default")
      (node (ref "C6-7") (pin "2") (pinfunction "2_2") (pintype "passive"))
      (node (ref "J4") (pin "19") (pinfunction "19_19") (pintype "passive"))
    )
    (net (code "33") (name "Net-(C6-8-Pad2)") (class "Default")
      (node (ref "C6-8") (pin "2") (pinfunction "2_2") (pintype "passive"))
      (node (ref "J4") (pin "20") (pinfunction "20_20") (pintype "passive"))
    )
    (net (code "34") (name "Net-(C6-10-Pad2)") (class "Default")
      (node (ref "C6-10") (pin "2") (pinfunction "2_2") (pintype "passive"))
      (node (ref "J4") (pin "22") (pinfunction "22_22") (pintype "passive"))
    )
    (net (code "35") (name "Net-(C6-12-Pad2)") (class "Default")
      (node (ref "C6-12") (pin "2") (pinfunction "2_2") (pintype "passive"))
      (node (ref "J4") (pin "24") (pinfunction "24_24") (pintype "passive"))
    )
    (net (code "36") (name "Net-(D3-1-K)") (class "Default")
      (node (ref "D3-1") (pin "2") (pinfunction "K_2") (pintype "passive"))
      (node (ref "Q3-1") (pin "3") (pinfunction "D_3") (pintype "passive"))
      (node (ref "SW") (pin "2") (pinfunction "2_2") (pintype "passive"))
    )
    (net (code "37") (name "Net-(LED9-1-A)") (class "Default")
      (node (ref "LED9-1") (pin "2") (pinfunction "A_2") (pintype "passive"))
      (node (ref "R9-1") (pin "1") (pinfunction "1_1") (pintype "passive"))
    )
    (net (code "38") (name "Net-(LED9-2-A)") (class "Default")
      (node (ref "LED9-2") (pin "2") (pinfunction "A_2") (pintype "passive"))
      (node (ref "R9-2") (pin "1") (pinfunction "1_1") (pintype "passive"))
    )
    (net (code "39") (name "Net-(LED9-3-A)") (class "Default")
      (node (ref "LED9-3") (pin "2") (pinfunction "A_2") (pintype "passive"))
      (node (ref "R9-3") (pin "1") (pinfunction "1_1") (pintype "passive"))
    )
    (net (code "40") (name "Net-(Q5-1-B)") (class "Default")
      (node (ref "Q5-1") (pin "1") (pinfunction "B_1") (pintype "passive"))
      (node (ref "R5-1") (pin "2") (pinfunction "2_2") (pintype "passive"))
    )
    (net (code "41") (name "Net-(Q5-1-E)") (class "Default")
      (node (ref "Q5-1") (pin "2") (pinfunction "E_2") (pintype "passive"))
      (node (ref "R5-2") (pin "1") (pinfunction "1_1") (pintype "passive"))
      (node (ref "U5") (pin "13") (pinfunction "DTR#_13") (pintype "passive"))
    )
    (net (code "42") (name "Net-(Q5-2-B)") (class "Default")
      (node (ref "Q5-2") (pin "1") (pinfunction "B_1") (pintype "passive"))
      (node (ref "R5-2") (pin "2") (pinfunction "2_2") (pintype "passive"))
    )
    (net (code "43") (name "Net-(Q5-2-E)") (class "Default")
      (node (ref "Q5-2") (pin "2") (pinfunction "E_2") (pintype "passive"))
      (node (ref "R5-1") (pin "1") (pinfunction "1_1") (pintype "passive"))
      (node (ref "U5") (pin "14") (pinfunction "RTS#_14") (pintype "passive"))
    )
    (net (code "44") (name "Net-(Q6-1-D)") (class "Default")
      (node (ref "C6-2") (pin "1") (pinfunction "1_1") (pintype "passive"))
      (node (ref "D6-3") (pin "2") (pinfunction "2_2") (pintype "passive"))
      (node (ref "L1") (pin "2") (pinfunction "2_2") (pintype "passive"))
      (node (ref "Q6-1") (pin "3") (pinfunction "D_3") (pintype "passive"))
    )
    (net (code "45") (name "Net-(U3-1-CE)") (class "Default")
      (node (ref "R3-1") (pin "1") (pinfunction "1_1") (pintype "passive"))
      (node (ref "U3-1") (pin "4") (pinfunction "VCC_4") (pintype "passive"))
      (node (ref "U3-1") (pin "8") (pinfunction "CE_8") (pintype "passive"))
    )
    (net (code "46") (name "Net-(U3-1-PROG)") (class "Default")
      (node (ref "R3-2") (pin "2") (pinfunction "2_2") (pintype "passive"))
      (node (ref "U3-1") (pin "2") (pinfunction "PROG_2") (pintype "passive"))
    )
    (net (code "47") (name "Net-(U3-2-L1)") (class "Default")
      (node (ref "L2") (pin "1") (pinfunction "1_1") (pintype "passive"))
      (node (ref "U3-2") (pin "9") (pinfunction "L1_9") (pintype "passive"))
    )
    (net (code "48") (name "Net-(U3-2-L2)") (class "Default")
      (node (ref "L2") (pin "2") (pinfunction "2_2") (pintype "passive"))
      (node (ref "U3-2") (pin "7") (pinfunction "L2_7") (pintype "passive"))
    )
    (net (code "49") (name "Net-(U3-2-PG)") (class "Default")
      (node (ref "R3-6") (pin "1") (pinfunction "1_1") (pintype "passive"))
      (node (ref "U3-2") (pin "5") (pinfunction "PG_5") (pintype "passive"))
    )
    (net (code "50") (name "Net-(USB2-CC1)") (class "Default")
      (node (ref "R2-2") (pin "1") (pinfunction "1_1") (pintype "passive"))
      (node (ref "USB2") (pin "A5") (pinfunction "CC1_A5") (pintype "passive"))
    )
    (net (code "51") (name "Net-(USB2-CC2)") (class "Default")
      (node (ref "R2-1") (pin "1") (pinfunction "1_1") (pintype "passive"))
      (node (ref "USB2") (pin "B5") (pinfunction "CC2_B5") (pintype "passive"))
    )
    (net (code "52") (name "VIN") (class "Default")
      (node (ref "C3-1") (pin "2") (pinfunction "2_2") (pintype "passive"))
      (node (ref "C3-2") (pin "2") (pinfunction "2_2") (pintype "passive"))
      (node (ref "D3-1") (pin "1") (pinfunction "A_1") (pintype "passive"))
      (node (ref "Q3-1") (pin "1") (pinfunction "G_1") (pintype "passive"))
      (node (ref "R3-1") (pin "2") (pinfunction "2_2") (pintype "passive"))
      (node (ref "R3-3") (pin "2") (pinfunction "2_2") (pintype "passive"))
      (node (ref "R9-1") (pin "2") (pinfunction "2_2") (pintype "passive"))
      (node (ref "R9-2") (pin "2") (pinfunction "2_2") (pintype "passive"))
      (node (ref "U6") (pin "5") (pinfunction "5_5") (pintype "passive"))
      (node (ref "USB2") (pin "A4B9") (pinfunction "VBUS_A4B9") (pintype "passive"))
      (node (ref "USB2") (pin "B4A9") (pinfunction "VBUS_B4A9") (pintype "passive"))
    )
    (net (code "53") (name "VIN1") (class "Default")
      (node (ref "C3-3") (pin "2") (pinfunction "2_2") (pintype "passive"))
      (node (ref "C3-4") (pin "2") (pinfunction "2_2") (pintype "passive"))
      (node (ref "D3-2") (pin "2") (pinfunction "K_2") (pintype "passive"))
      (node (ref "R3-6") (pin "2") (pinfunction "2_2") (pintype "passive"))
      (node (ref "SW") (pin "1") (pinfunction "1_1") (pintype "passive"))
      (node (ref "U3-2") (pin "1") (pinfunction "EN_1") (pintype "passive"))
      (node (ref "U3-2") (pin "10") (pinfunction "VIN_10") (pintype "passive"))
    )
    (net (code "54") (name "unconnected-(BOOT-EP-Pad3)") (class "Default")
      (node (ref "BOOT") (pin "3") (pinfunction "EP_3") (pintype "passive+no_connect"))
    )
    (net (code "55") (name "unconnected-(BOOT-EP-Pad4)") (class "Default")
      (node (ref "BOOT") (pin "4") (pinfunction "EP_4") (pintype "passive+no_connect"))
    )
    (net (code "56") (name "unconnected-(J1-Pad3)") (class "Default")
      (node (ref "J1") (pin "3") (pinfunction "3_3") (pintype "passive+no_connect"))
    )
    (net (code "57") (name "unconnected-(J1-Pad4)") (class "Default")
      (node (ref "J1") (pin "4") (pinfunction "4_4") (pintype "passive+no_connect"))
    )
    (net (code "58") (name "unconnected-(J4-Pad1)") (class "Default")
      (node (ref "J4") (pin "1") (pinfunction "1_1") (pintype "passive+no_connect"))
    )
    (net (code "59") (name "unconnected-(J4-Pad6)") (class "Default")
      (node (ref "J4") (pin "6") (pinfunction "6_6") (pintype "passive+no_connect"))
    )
    (net (code "60") (name "unconnected-(J4-Pad7)") (class "Default")
      (node (ref "J4") (pin "7") (pinfunction "7_7") (pintype "passive+no_connect"))
    )
    (net (code "61") (name "unconnected-(J4-Pad25)") (class "Default")
      (node (ref "J4") (pin "25") (pinfunction "25_25") (pintype "passive+no_connect"))
    )
    (net (code "62") (name "unconnected-(J4-Pad26)") (class "Default")
      (node (ref "J4") (pin "26") (pinfunction "26_26") (pintype "passive+no_connect"))
    )
    (net (code "63") (name "unconnected-(KEY1-EP-Pad3)") (class "Default")
      (node (ref "KEY1") (pin "3") (pinfunction "EP_3") (pintype "passive+no_connect"))
    )
    (net (code "64") (name "unconnected-(KEY1-EP-Pad4)") (class "Default")
      (node (ref "KEY1") (pin "4") (pinfunction "EP_4") (pintype "passive+no_connect"))
    )
    (net (code "65") (name "unconnected-(KEY2-EP-Pad3)") (class "Default")
      (node (ref "KEY2") (pin "3") (pinfunction "EP_3") (pintype "passive+no_connect"))
    )
    (net (code "66") (name "unconnected-(KEY2-EP-Pad4)") (class "Default")
      (node (ref "KEY2") (pin "4") (pinfunction "EP_4") (pintype "passive+no_connect"))
    )
    (net (code "67") (name "unconnected-(RST-EP-Pad3)") (class "Default")
      (node (ref "RST") (pin "3") (pinfunction "EP_3") (pintype "passive+no_connect"))
    )
    (net (code "68") (name "unconnected-(RST-EP-Pad4)") (class "Default")
      (node (ref "RST") (pin "4") (pinfunction "EP_4") (pintype "passive+no_connect"))
    )
    (net (code "69") (name "unconnected-(SW-Pad3)") (class "Default")
      (node (ref "SW") (pin "3") (pinfunction "3_3") (pintype "passive+no_connect"))
    )
    (net (code "70") (name "unconnected-(SW-Pad4)") (class "Default")
      (node (ref "SW") (pin "4") (pinfunction "4_4") (pintype "passive+no_connect"))
    )
    (net (code "71") (name "unconnected-(SW-Pad4)_1") (class "Default")
      (node (ref "SW") (pin "4") (pinfunction "4_4") (pintype "passive+no_connect"))
    )
    (net (code "72") (name "unconnected-(SW-Pad4)_2") (class "Default")
      (node (ref "SW") (pin "4") (pinfunction "4_4") (pintype "passive+no_connect"))
    )
    (net (code "73") (name "unconnected-(SW-Pad4)_3") (class "Default")
      (node (ref "SW") (pin "4") (pinfunction "4_4") (pintype "passive+no_connect"))
    )
    (net (code "74") (name "unconnected-(U4-ALERT-Pad3)") (class "Default")
      (node (ref "U4") (pin "3") (pinfunction "ALERT_3") (pintype "passive+no_connect"))
    )
    (net (code "75") (name "unconnected-(U4-nRESET-Pad6)") (class "Default")
      (node (ref "U4") (pin "6") (pinfunction "nRESET_6") (pintype "passive+no_connect"))
    )
    (net (code "76") (name "unconnected-(U5-CTS#-Pad9)") (class "Default")
      (node (ref "U5") (pin "9") (pinfunction "CTS#_9") (pintype "passive+no_connect"))
    )
    (net (code "77") (name "unconnected-(U5-DCD#-Pad12)") (class "Default")
      (node (ref "U5") (pin "12") (pinfunction "DCD#_12") (pintype "passive+no_connect"))
    )
    (net (code "78") (name "unconnected-(U5-DSR#-Pad10)") (class "Default")
      (node (ref "U5") (pin "10") (pinfunction "DSR#_10") (pintype "passive+no_connect"))
    )
    (net (code "79") (name "unconnected-(U5-NC.-Pad7)") (class "Default")
      (node (ref "U5") (pin "7") (pinfunction "NC._7") (pintype "passive+no_connect"))
    )
    (net (code "80") (name "unconnected-(U5-NC.-Pad8)") (class "Default")
      (node (ref "U5") (pin "8") (pinfunction "NC._8") (pintype "passive+no_connect"))
    )
    (net (code "81") (name "unconnected-(U5-R232-Pad15)") (class "Default")
      (node (ref "U5") (pin "15") (pinfunction "R232_15") (pintype "passive+no_connect"))
    )
    (net (code "82") (name "unconnected-(U5-RI#-Pad11)") (class "Default")
      (node (ref "U5") (pin "11") (pinfunction "RI#_11") (pintype "passive+no_connect"))
    )
    (net (code "83") (name "unconnected-(U6-Pad3)") (class "Default")
      (node (ref "U6") (pin "3") (pinfunction "3_3") (pintype "passive+no_connect"))
    )
    (net (code "84") (name "unconnected-(U6-Pad4)") (class "Default")
      (node (ref "U6") (pin "4") (pinfunction "4_4") (pintype "passive+no_connect"))
    )
    (net (code "85") (name "unconnected-(USB2-SBU1-PadA8)") (class "Default")
      (node (ref "USB2") (pin "A8") (pinfunction "SBU1_A8") (pintype "passive+no_connect"))
    )
    (net (code "86") (name "unconnected-(USB2-SBU2-PadB8)") (class "Default")
      (node (ref "USB2") (pin "B8") (pinfunction "SBU2_B8") (pintype "passive+no_connect"))
    )
  )
)
